# GTM_CANconnector.net
KiCad netlist of a schematic drawn in Altium Designer
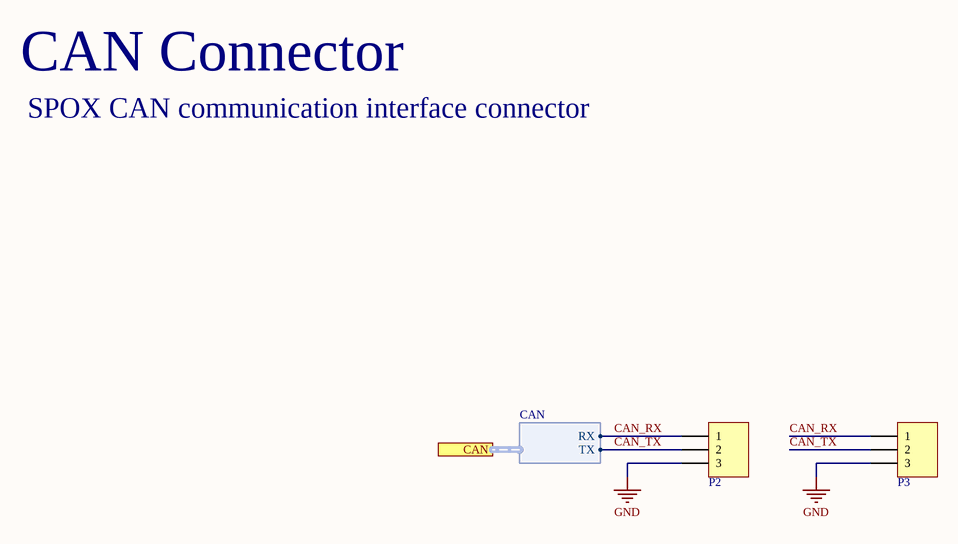
[diagram p0: GTM_CANconnector.SchDoc]

(export (version "E")
  (design (tool "Eeschema 10.0.6"))
  (components
    (comp (ref "P2")
      (value "HDR1X3")
      (footprint "HDR1X3")
      (description "Header, 3-Pin")
      (fields (field (name "PUBLISHER") "Altium Limited"))
      (libsource (lib "Library_Altium_KNR") (part "HDR1X3"))
    )
    (comp (ref "P3")
      (value "Doubled Connector")
      (footprint "HDR1X3")
      (description "Header, 3-Pin")
      (fields (field (name "PUBLISHER") "Altium Limited"))
      (libsource (lib "Library_Altium_KNR") (part "HDR1X3"))
    )
  )
  (nets
    (net (code "2") (name "/CAN_RX") (class "Default")
      (node (ref "P2") (pin "1") (pinfunction "1_1") (pintype "passive"))
      (node (ref "P3") (pin "1") (pinfunction "1_1") (pintype "passive"))
    )
    (net (code "3") (name "/CAN_TX") (class "Default")
      (node (ref "P2") (pin "2") (pinfunction "2_2") (pintype "passive"))
      (node (ref "P3") (pin "2") (pinfunction "2_2") (pintype "passive"))
    )
    (net (code "5") (name "GND") (class "Default")
      (node (ref "P2") (pin "3") (pinfunction "3_3") (pintype "passive"))
      (node (ref "P3") (pin "3") (pinfunction "3_3") (pintype "passive"))
    )
  )
)
